# Sheet2.net
KiCad netlist of a schematic drawn in Altium Designer
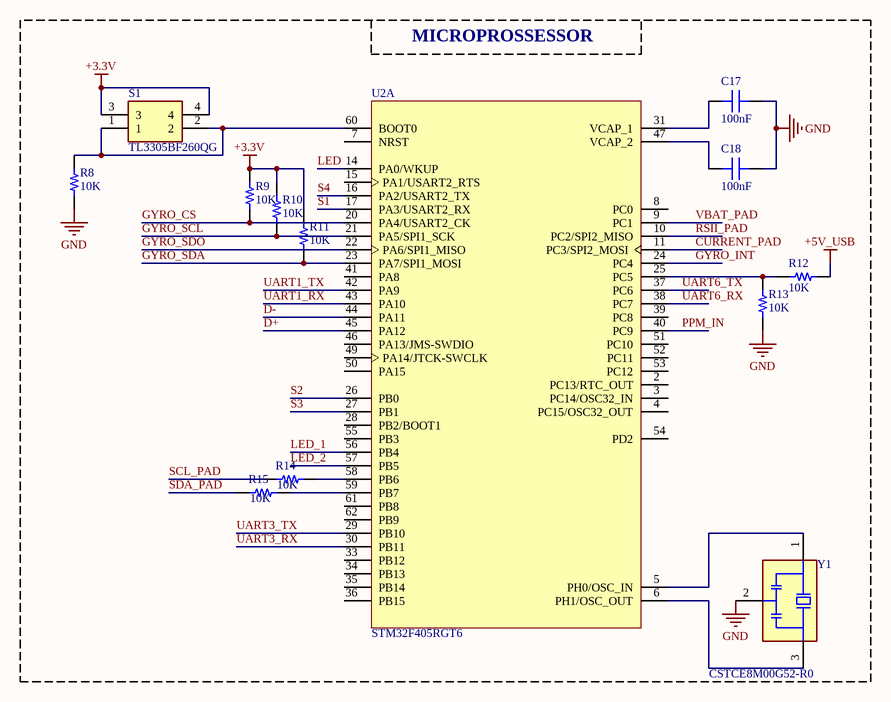
[diagram p0: Sheet2.SchDoc]

(export (version "E")
  (design (tool "Eeschema 10.0.6"))
  (components
    (comp (ref "C17")
      (value "100nF")
      (footprint "CAP-0603")
      (description "Cap Ceramic 0.1uF 50V X7R 10% SMD 0603 125°C Paper T/R 100nF")
      (fields
        (field (name "MANUFACTURER") "KEMET")
        (field (name "MANUFACTURER PART NUMBER") "C0603C104K5RAC7411")
      )
      (libsource (lib "Schlib1") (part "C0603C104K5RAC7411"))
    )
    (comp (ref "C18")
      (value "100nF")
      (footprint "CAP-0603")
      (description "Cap Ceramic 0.1uF 50V X7R 10% SMD 0603 125°C Paper T/R 100nF")
      (fields
        (field (name "MANUFACTURER") "KEMET")
        (field (name "MANUFACTURER PART NUMBER") "C0603C104K5RAC7411")
      )
      (libsource (lib "Schlib1") (part "C0603C104K5RAC7411"))
    )
    (comp (ref "R8")
      (value "10K")
      (footprint "RES-0603")
      (description "10 kOhms ±1% 0.1W, 1/10W Chip Resistor 0603 (1608 Metric) Moisture Resistant Thick Film")
      (fields
        (field (name "MANUFACTURER") "Yageo")
        (field (name "MANUFACTURER PART NUMBER") "RC0603FR-0710KL")
      )
      (libsource (lib "Schlib1") (part "RC0603FR-0710KL"))
    )
    (comp (ref "R9")
      (value "10K")
      (footprint "RES-0603")
      (description "10 kOhms ±1% 0.1W, 1/10W Chip Resistor 0603 (1608 Metric) Moisture Resistant Thick Film")
      (fields
        (field (name "MANUFACTURER") "Yageo")
        (field (name "MANUFACTURER PART NUMBER") "RC0603FR-0710KL")
      )
      (libsource (lib "Schlib1") (part "RC0603FR-0710KL"))
    )
    (comp (ref "R10")
      (value "10K")
      (footprint "RES-0603")
      (description "10 kOhms ±1% 0.1W, 1/10W Chip Resistor 0603 (1608 Metric) Moisture Resistant Thick Film")
      (fields
        (field (name "MANUFACTURER") "Yageo")
        (field (name "MANUFACTURER PART NUMBER") "RC0603FR-0710KL")
      )
      (libsource (lib "Schlib1") (part "RC0603FR-0710KL"))
    )
    (comp (ref "R11")
      (value "10K")
      (footprint "RES-0603")
      (description "10 kOhms ±1% 0.1W, 1/10W Chip Resistor 0603 (1608 Metric) Moisture Resistant Thick Film")
      (fields
        (field (name "MANUFACTURER") "Yageo")
        (field (name "MANUFACTURER PART NUMBER") "RC0603FR-0710KL")
      )
      (libsource (lib "Schlib1") (part "RC0603FR-0710KL"))
    )
    (comp (ref "R12")
      (value "10K")
      (footprint "RES-0603")
      (description "10 kOhms ±1% 0.1W, 1/10W Chip Resistor 0603 (1608 Metric) Moisture Resistant Thick Film")
      (fields
        (field (name "MANUFACTURER") "Yageo")
        (field (name "MANUFACTURER PART NUMBER") "RC0603FR-0710KL")
      )
      (libsource (lib "Schlib1") (part "RC0603FR-0710KL"))
    )
    (comp (ref "R13")
      (value "10K")
      (footprint "RES-0603")
      (description "10 kOhms ±1% 0.1W, 1/10W Chip Resistor 0603 (1608 Metric) Moisture Resistant Thick Film")
      (fields
        (field (name "MANUFACTURER") "Yageo")
        (field (name "MANUFACTURER PART NUMBER") "RC0603FR-0710KL")
      )
      (libsource (lib "Schlib1") (part "RC0603FR-0710KL"))
    )
    (comp (ref "R14")
      (value "10K")
      (footprint "RES-0603")
      (description "10 kOhms ±1% 0.1W, 1/10W Chip Resistor 0603 (1608 Metric) Moisture Resistant Thick Film")
      (fields
        (field (name "MANUFACTURER") "Yageo")
        (field (name "MANUFACTURER PART NUMBER") "RC0603FR-0710KL")
      )
      (libsource (lib "Schlib1") (part "RC0603FR-0710KL"))
    )
    (comp (ref "R15")
      (value "10K")
      (footprint "RES-0603")
      (description "10 kOhms ±1% 0.1W, 1/10W Chip Resistor 0603 (1608 Metric) Moisture Resistant Thick Film")
      (fields
        (field (name "MANUFACTURER") "Yageo")
        (field (name "MANUFACTURER PART NUMBER") "RC0603FR-0710KL")
      )
      (libsource (lib "Schlib1") (part "RC0603FR-0710KL"))
    )
    (comp (ref "S1")
      (value "TL3305BF260QG")
      (footprint "TL3305BF260QG")
      (description "Switch")
      (fields (field (name "MOUSER PART NUMBER") "612-TL3305BF260QG"))
      (libsource (lib "Schlib1") (part "TL3305BF260QG"))
    )
    (comp (ref "U2")
      (value "STM32F405RGT6")
      (footprint "STMicroelectronics_LQFP64-5W_MFG")
      (description "ARMÂ® CortexÂ®-M4 STM32F4 Microcontroller IC 32-Bit 168MHz 1MB _1M x 8_ FLASH 64-LQFP _10x10_")
      (fields (field (name "MF") "STMicroelectronics") (field (name "DIGI-KEY_PART_NUMBER") "497-11767-ND"))
      (libsource (lib "Schlib1") (part "STM32F405RGT6"))
    )
    (comp (ref "Y1")
      (value "CSTCE8M00G52-R0")
      (footprint "OSC_CSTCE8M00G52-R0")
      (description "8MHz Ceramic Resonator Built in Capacitor 10pF Â±0.2% -20Â°C ~ 80Â°C Surface Mount")
      (fields (field (name "MF") "Murata"))
      (libsource (lib "Schlib1") (part "CSTCE8M00G52-R0"))
    )
  )
  (nets
    (net (code "1") (name "+3.3V") (class "Default")
      (node (ref "R10") (pin "2") (pinfunction "2_2") (pintype "passive"))
      (node (ref "R11") (pin "2") (pinfunction "2_2") (pintype "passive"))
      (node (ref "R9") (pin "2") (pinfunction "2_2") (pintype "passive"))
      (node (ref "S1") (pin "3") (pinfunction "3_3") (pintype "passive"))
      (node (ref "S1") (pin "4") (pinfunction "4_4") (pintype "passive"))
    )
    (net (code "2") (name "+5V_USB") (class "Default")
      (node (ref "R12") (pin "2") (pinfunction "2_2") (pintype "passive"))
    )
    (net (code "3") (name "/CURRENT_PAD") (class "Default")
      (node (ref "U2") (pin "11") (pinfunction "PC3/SPI2_MOSI_11") (pintype "passive"))
    )
    (net (code "4") (name "/D+") (class "Default")
      (node (ref "U2") (pin "45") (pinfunction "PA12_45") (pintype "passive"))
    )
    (net (code "5") (name "/D-") (class "Default")
      (node (ref "U2") (pin "44") (pinfunction "PA11_44") (pintype "passive"))
    )
    (net (code "6") (name "/GYRO_CS") (class "Default")
      (node (ref "R9") (pin "1") (pinfunction "1_1") (pintype "passive"))
      (node (ref "U2") (pin "20") (pinfunction "PA4/USART2_CK_20") (pintype "passive"))
    )
    (net (code "7") (name "/GYRO_INT") (class "Default")
      (node (ref "U2") (pin "24") (pinfunction "PC4_24") (pintype "passive"))
    )
    (net (code "8") (name "/GYRO_SCL") (class "Default")
      (node (ref "R10") (pin "1") (pinfunction "1_1") (pintype "passive"))
      (node (ref "U2") (pin "21") (pinfunction "PA5/SPI1_SCK_21") (pintype "passive"))
    )
    (net (code "9") (name "/GYRO_SDA") (class "Default")
      (node (ref "R11") (pin "1") (pinfunction "1_1") (pintype "passive"))
      (node (ref "U2") (pin "23") (pinfunction "PA7/SPI1_MOSI_23") (pintype "passive"))
    )
    (net (code "10") (name "/GYRO_SDO") (class "Default")
      (node (ref "U2") (pin "22") (pinfunction "PA6/SPI1_MISO_22") (pintype "passive"))
    )
    (net (code "11") (name "/LED") (class "Default")
      (node (ref "U2") (pin "14") (pinfunction "PA0/WKUP_14") (pintype "passive"))
    )
    (net (code "12") (name "/LED_1") (class "Default")
      (node (ref "U2") (pin "56") (pinfunction "PB4_56") (pintype "passive"))
    )
    (net (code "13") (name "/LED_2") (class "Default")
      (node (ref "U2") (pin "57") (pinfunction "PB5_57") (pintype "passive"))
    )
    (net (code "14") (name "/PPM_IN") (class "Default")
      (node (ref "U2") (pin "40") (pinfunction "PC9_40") (pintype "passive"))
    )
    (net (code "15") (name "/RSII_PAD") (class "Default")
      (node (ref "U2") (pin "10") (pinfunction "PC2/SPI2_MISO_10") (pintype "passive"))
    )
    (net (code "16") (name "/S1") (class "Default")
      (node (ref "U2") (pin "17") (pinfunction "PA3/USART2_RX_17") (pintype "passive"))
    )
    (net (code "17") (name "/S2") (class "Default")
      (node (ref "U2") (pin "26") (pinfunction "PB0_26") (pintype "passive"))
    )
    (net (code "18") (name "/S3") (class "Default")
      (node (ref "U2") (pin "27") (pinfunction "PB1_27") (pintype "passive"))
    )
    (net (code "19") (name "/S4") (class "Default")
      (node (ref "U2") (pin "16") (pinfunction "PA2/USART2_TX_16") (pintype "passive"))
    )
    (net (code "20") (name "/SCL_PAD") (class "Default")
      (node (ref "R14") (pin "1") (pinfunction "1_1") (pintype "passive"))
    )
    (net (code "21") (name "/SDA_PAD") (class "Default")
      (node (ref "R15") (pin "1") (pinfunction "1_1") (pintype "passive"))
    )
    (net (code "22") (name "/UART1_RX") (class "Default")
      (node (ref "U2") (pin "43") (pinfunction "PA10_43") (pintype "passive"))
    )
    (net (code "23") (name "/UART1_TX") (class "Default")
      (node (ref "U2") (pin "42") (pinfunction "PA9_42") (pintype "passive"))
    )
    (net (code "24") (name "/UART3_RX") (class "Default")
      (node (ref "U2") (pin "30") (pinfunction "PB11_30") (pintype "passive"))
    )
    (net (code "25") (name "/UART3_TX") (class "Default")
      (node (ref "U2") (pin "29") (pinfunction "PB10_29") (pintype "passive"))
    )
    (net (code "26") (name "/UART6_RX") (class "Default")
      (node (ref "U2") (pin "38") (pinfunction "PC7_38") (pintype "passive"))
    )
    (net (code "27") (name "/UART6_TX") (class "Default")
      (node (ref "U2") (pin "37") (pinfunction "PC6_37") (pintype "passive"))
    )
    (net (code "28") (name "/VBAT_PAD") (class "Default")
      (node (ref "U2") (pin "9") (pinfunction "PC1_9") (pintype "passive"))
    )
    (net (code "29") (name "GND") (class "Default")
      (node (ref "C17") (pin "1") (pinfunction "1_1") (pintype "passive"))
      (node (ref "C18") (pin "1") (pinfunction "1_1") (pintype "passive"))
      (node (ref "R13") (pin "1") (pinfunction "1_1") (pintype "passive"))
      (node (ref "R8") (pin "1") (pinfunction "1_1") (pintype "passive"))
      (node (ref "Y1") (pin "2") (pinfunction "GND_2") (pintype "power_in"))
    )
    (net (code "30") (name "Net-(U2A-BOOT0)") (class "Default")
      (node (ref "R8") (pin "2") (pinfunction "2_2") (pintype "passive"))
      (node (ref "S1") (pin "1") (pinfunction "1_1") (pintype "passive"))
      (node (ref "S1") (pin "2") (pinfunction "2_2") (pintype "passive"))
      (node (ref "U2") (pin "60") (pinfunction "BOOT0_60") (pintype "passive"))
    )
    (net (code "31") (name "Net-(U2A-PB6)") (class "Default")
      (node (ref "R14") (pin "2") (pinfunction "2_2") (pintype "passive"))
      (node (ref "U2") (pin "58") (pinfunction "PB6_58") (pintype "passive"))
    )
    (net (code "32") (name "Net-(U2A-PB7)") (class "Default")
      (node (ref "R15") (pin "2") (pinfunction "2_2") (pintype "passive"))
      (node (ref "U2") (pin "59") (pinfunction "PB7_59") (pintype "passive"))
    )
    (net (code "33") (name "Net-(U2A-PC5)") (class "Default")
      (node (ref "R12") (pin "1") (pinfunction "1_1") (pintype "passive"))
      (node (ref "R13") (pin "2") (pinfunction "2_2") (pintype "passive"))
      (node (ref "U2") (pin "25") (pinfunction "PC5_25") (pintype "passive"))
    )
    (net (code "34") (name "Net-(U2A-PH0{slash}OSC_IN)") (class "Default")
      (node (ref "U2") (pin "5") (pinfunction "PH0/OSC_IN_5") (pintype "passive"))
      (node (ref "Y1") (pin "1") (pinfunction "IN_1") (pintype "passive"))
    )
    (net (code "35") (name "Net-(U2A-PH1{slash}OSC_OUT)") (class "Default")
      (node (ref "U2") (pin "6") (pinfunction "PH1/OSC_OUT_6") (pintype "passive"))
      (node (ref "Y1") (pin "3") (pinfunction "OUT_3") (pintype "passive"))
    )
    (net (code "36") (name "Net-(U2A-VCAP_1)") (class "Default")
      (node (ref "C17") (pin "2") (pinfunction "2_2") (pintype "passive"))
      (node (ref "U2") (pin "31") (pinfunction "VCAP_1_31") (pintype "passive"))
    )
    (net (code "37") (name "Net-(U2A-VCAP_2)") (class "Default")
      (node (ref "C18") (pin "2") (pinfunction "2_2") (pintype "passive"))
      (node (ref "U2") (pin "47") (pinfunction "VCAP_2_47") (pintype "passive"))
    )
    (net (code "38") (name "unconnected-(U2A-NRST-Pad7)") (class "Default")
      (node (ref "U2") (pin "7") (pinfunction "NRST_7") (pintype "passive"))
    )
    (net (code "39") (name "unconnected-(U2A-PA1{slash}USART2_RTS-Pad15)") (class "Default")
      (node (ref "U2") (pin "15") (pinfunction "PA1/USART2_RTS_15") (pintype "passive"))
    )
    (net (code "40") (name "unconnected-(U2A-PA8-Pad41)") (class "Default")
      (node (ref "U2") (pin "41") (pinfunction "PA8_41") (pintype "passive"))
    )
    (net (code "41") (name "unconnected-(U2A-PA13{slash}JMS-SWDIO-Pad46)") (class "Default")
      (node (ref "U2") (pin "46") (pinfunction "PA13/JMS-SWDIO_46") (pintype "passive"))
    )
    (net (code "42") (name "unconnected-(U2A-PA14{slash}JTCK-SWCLK-Pad49)") (class "Default")
      (node (ref "U2") (pin "49") (pinfunction "PA14/JTCK-SWCLK_49") (pintype "passive"))
    )
    (net (code "43") (name "unconnected-(U2A-PA15-Pad50)") (class "Default")
      (node (ref "U2") (pin "50") (pinfunction "PA15_50") (pintype "passive"))
    )
    (net (code "44") (name "unconnected-(U2A-PB2{slash}BOOT1-Pad28)") (class "Default")
      (node (ref "U2") (pin "28") (pinfunction "PB2/BOOT1_28") (pintype "passive"))
    )
    (net (code "45") (name "unconnected-(U2A-PB3-Pad55)") (class "Default")
      (node (ref "U2") (pin "55") (pinfunction "PB3_55") (pintype "passive"))
    )
    (net (code "46") (name "unconnected-(U2A-PB8-Pad61)") (class "Default")
      (node (ref "U2") (pin "61") (pinfunction "PB8_61") (pintype "passive"))
    )
    (net (code "47") (name "unconnected-(U2A-PB9-Pad62)") (class "Default")
      (node (ref "U2") (pin "62") (pinfunction "PB9_62") (pintype "passive"))
    )
    (net (code "48") (name "unconnected-(U2A-PB12-Pad33)") (class "Default")
      (node (ref "U2") (pin "33") (pinfunction "PB12_33") (pintype "passive"))
    )
    (net (code "49") (name "unconnected-(U2A-PB13-Pad34)") (class "Default")
      (node (ref "U2") (pin "34") (pinfunction "PB13_34") (pintype "passive"))
    )
    (net (code "50") (name "unconnected-(U2A-PB14-Pad35)") (class "Default")
      (node (ref "U2") (pin "35") (pinfunction "PB14_35") (pintype "passive"))
    )
    (net (code "51") (name "unconnected-(U2A-PB15-Pad36)") (class "Default")
      (node (ref "U2") (pin "36") (pinfunction "PB15_36") (pintype "passive"))
    )
    (net (code "52") (name "unconnected-(U2A-PC0-Pad8)") (class "Default")
      (node (ref "U2") (pin "8") (pinfunction "PC0_8") (pintype "passive"))
    )
    (net (code "53") (name "unconnected-(U2A-PC8-Pad39)") (class "Default")
      (node (ref "U2") (pin "39") (pinfunction "PC8_39") (pintype "passive"))
    )
    (net (code "54") (name "unconnected-(U2A-PC10-Pad51)") (class "Default")
      (node (ref "U2") (pin "51") (pinfunction "PC10_51") (pintype "passive"))
    )
    (net (code "55") (name "unconnected-(U2A-PC11-Pad52)") (class "Default")
      (node (ref "U2") (pin "52") (pinfunction "PC11_52") (pintype "passive"))
    )
    (net (code "56") (name "unconnected-(U2A-PC12-Pad53)") (class "Default")
      (node (ref "U2") (pin "53") (pinfunction "PC12_53") (pintype "passive"))
    )
    (net (code "57") (name "unconnected-(U2A-PC13{slash}RTC_OUT-Pad2)") (class "Default")
      (node (ref "U2") (pin "2") (pinfunction "PC13/RTC_OUT_2") (pintype "passive"))
    )
    (net (code "58") (name "unconnected-(U2A-PC14{slash}OSC32_IN-Pad3)") (class "Default")
      (node (ref "U2") (pin "3") (pinfunction "PC14/OSC32_IN_3") (pintype "passive"))
    )
    (net (code "59") (name "unconnected-(U2A-PC15{slash}OSC32_OUT-Pad4)") (class "Default")
      (node (ref "U2") (pin "4") (pinfunction "PC15/OSC32_OUT_4") (pintype "passive"))
    )
    (net (code "60") (name "unconnected-(U2A-PD2-Pad54)") (class "Default")
      (node (ref "U2") (pin "54") (pinfunction "PD2_54") (pintype "passive"))
    )
  )
)
